# 3_Sensor.net
KiCad netlist of a schematic drawn in Altium Designer
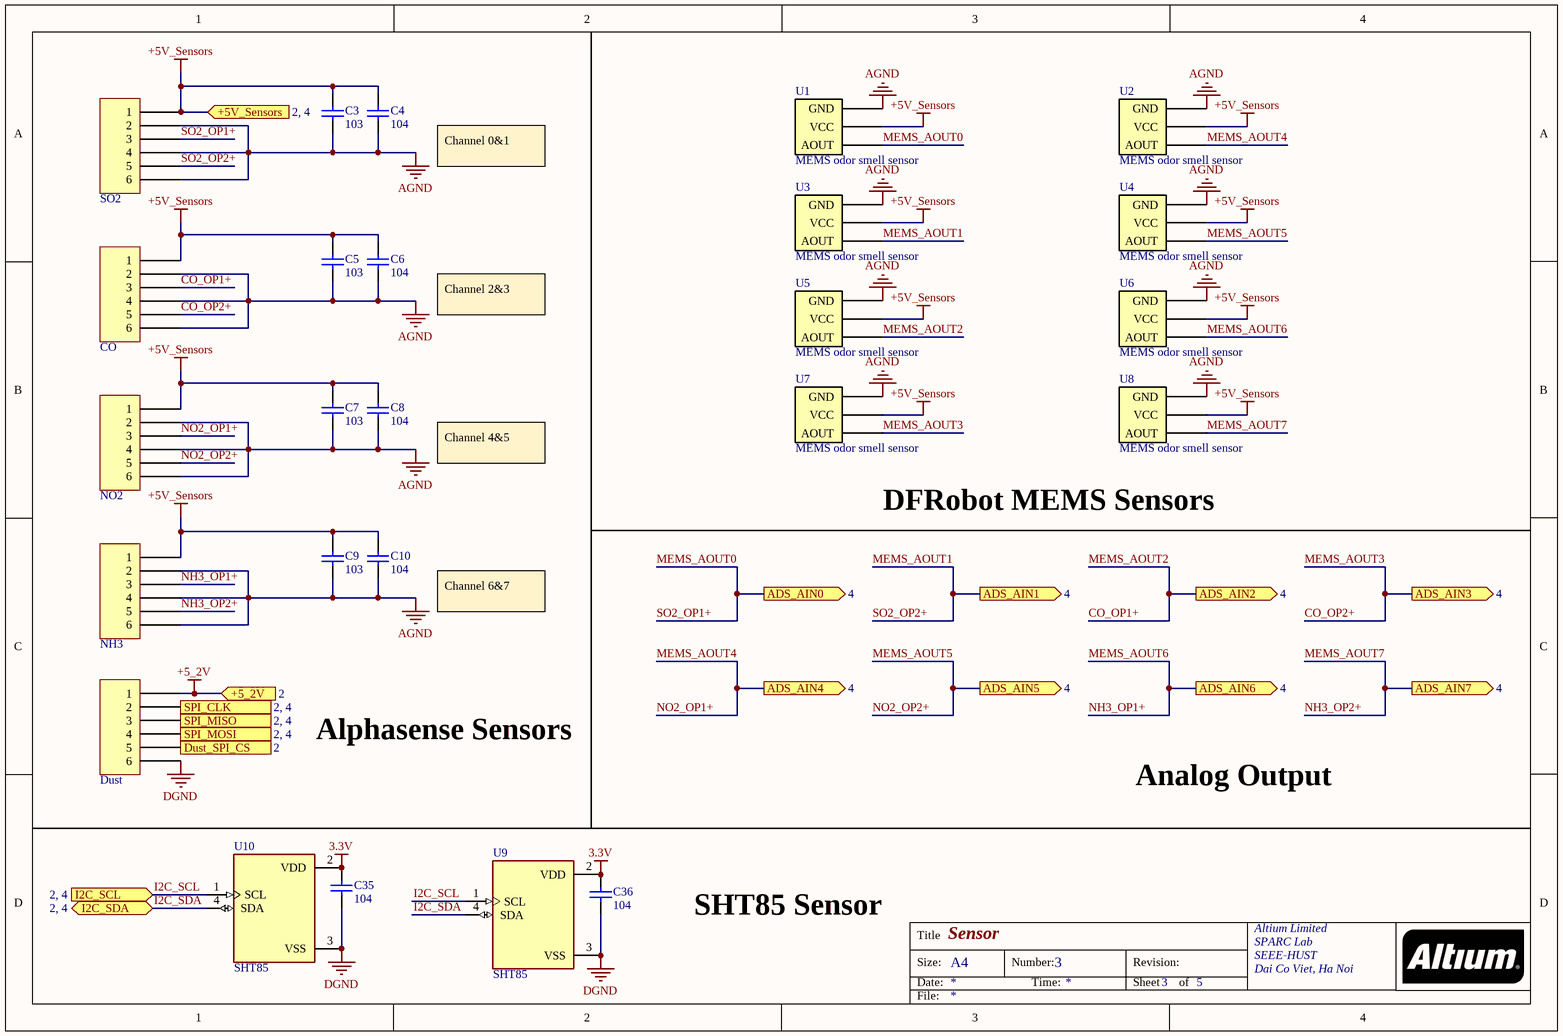
[diagram p0: [3]Sensor.SchDoc]

(export (version "E")
  (design (tool "Eeschema 10.0.6"))
  (components
    (comp (ref "C3")
      (value "103")
      (footprint "tu 0805")
      (description "Dán")
      (libsource (lib "Tu dien") (part "Tu 0805 103 50V 10%_1"))
    )
    (comp (ref "C4")
      (value "104")
      (footprint "tu 0805")
      (description "Dán")
      (libsource (lib "Tu dien") (part "Tu 0805 104 50V 10%"))
    )
    (comp (ref "C5")
      (value "103")
      (footprint "tu 0805")
      (description "Dán")
      (libsource (lib "Tu dien") (part "Tu 0805 103 50V 10%_1"))
    )
    (comp (ref "C6")
      (value "104")
      (footprint "tu 0805")
      (description "Dán")
      (libsource (lib "Tu dien") (part "Tu 0805 104 50V 10%"))
    )
    (comp (ref "C7")
      (value "103")
      (footprint "tu 0805")
      (description "Dán")
      (libsource (lib "Tu dien") (part "Tu 0805 103 50V 10%_1"))
    )
    (comp (ref "C8")
      (value "104")
      (footprint "tu 0805")
      (description "Dán")
      (libsource (lib "Tu dien") (part "Tu 0805 104 50V 10%"))
    )
    (comp (ref "C9")
      (value "103")
      (footprint "tu 0805")
      (description "Dán")
      (libsource (lib "Tu dien") (part "Tu 0805 103 50V 10%_1"))
    )
    (comp (ref "C10")
      (value "104")
      (footprint "tu 0805")
      (description "Dán")
      (libsource (lib "Tu dien") (part "Tu 0805 104 50V 10%"))
    )
    (comp (ref "C35")
      (value "104")
      (footprint "tu 0805")
      (description "Dán")
      (libsource (lib "Tu dien") (part "Tu 0805 104 50V 10%"))
    )
    (comp (ref "C36")
      (value "104")
      (footprint "tu 0805")
      (description "Dán")
      (libsource (lib "Tu dien") (part "Tu 0805 104 50V 10%"))
    )
    (comp (ref "H1") (value "SO2") (footprint "Header:Molex 6p") (libsource (lib "Header") (part "Molex 6p")))
    (comp (ref "H2") (value "CO") (footprint "Header:Molex 6p") (libsource (lib "Header") (part "Molex 6p")))
    (comp (ref "H3") (value "NO2") (footprint "Header:Molex 6p") (libsource (lib "Header") (part "Molex 6p")))
    (comp (ref "H4") (value "NH3") (footprint "Header:Molex 6p") (libsource (lib "Header") (part "Molex 6p")))
    (comp (ref "H5")
      (value "Dust")
      (footprint "Header:Molex 6p")
      (libsource (lib "Header") (part "Molex 6p"))
    )
    (comp (ref "U1")
      (value "MEMS odor smell sensor")
      (footprint "Module1:MEMS_odor_sensor")
      (description "DFRobot MEMS Odor Smell Gas Detection Sensor")
      (libsource (lib "Module1") (part "MEMS odor smell sensor"))
    )
    (comp (ref "U2")
      (value "MEMS odor smell sensor")
      (footprint "Module1:MEMS_odor_sensor")
      (description "DFRobot MEMS Odor Smell Gas Detection Sensor")
      (libsource (lib "Module1") (part "MEMS odor smell sensor"))
    )
    (comp (ref "U3")
      (value "MEMS odor smell sensor")
      (footprint "Module1:MEMS_odor_sensor")
      (description "DFRobot MEMS Odor Smell Gas Detection Sensor")
      (libsource (lib "Module1") (part "MEMS odor smell sensor"))
    )
    (comp (ref "U4")
      (value "MEMS odor smell sensor")
      (footprint "Module1:MEMS_odor_sensor")
      (description "DFRobot MEMS Odor Smell Gas Detection Sensor")
      (libsource (lib "Module1") (part "MEMS odor smell sensor"))
    )
    (comp (ref "U5")
      (value "MEMS odor smell sensor")
      (footprint "Module1:MEMS_odor_sensor")
      (description "DFRobot MEMS Odor Smell Gas Detection Sensor")
      (libsource (lib "Module1") (part "MEMS odor smell sensor"))
    )
    (comp (ref "U6")
      (value "MEMS odor smell sensor")
      (footprint "Module1:MEMS_odor_sensor")
      (description "DFRobot MEMS Odor Smell Gas Detection Sensor")
      (libsource (lib "Module1") (part "MEMS odor smell sensor"))
    )
    (comp (ref "U7")
      (value "MEMS odor smell sensor")
      (footprint "Module1:MEMS_odor_sensor")
      (description "DFRobot MEMS Odor Smell Gas Detection Sensor")
      (libsource (lib "Module1") (part "MEMS odor smell sensor"))
    )
    (comp (ref "U8")
      (value "MEMS odor smell sensor")
      (footprint "Module1:MEMS_odor_sensor")
      (description "DFRobot MEMS Odor Smell Gas Detection Sensor")
      (libsource (lib "Module1") (part "MEMS odor smell sensor"))
    )
    (comp (ref "U9")
      (value "SHT85")
      (footprint "Module1:XDCR_SHT85")
      (description "Humidity Temperature Sensor 0 ~ 100% RH Digital Â±1.5% RH 8s Through Hole")
      (fields (field (name "MF") "Sensirion AG") (field (name "DIGI-KEY_PART_NUMBER") "1649-1110-ND"))
      (libsource (lib "Module1") (part "SHT85"))
    )
    (comp (ref "U10")
      (value "SHT85")
      (footprint "Module1:XDCR_SHT85")
      (description "Humidity Temperature Sensor 0 ~ 100% RH Digital Â±1.5% RH 8s Through Hole")
      (fields (field (name "MF") "Sensirion AG") (field (name "DIGI-KEY_PART_NUMBER") "1649-1110-ND"))
      (libsource (lib "Module1") (part "SHT85"))
    )
  )
  (nets
    (net (code "1") (name "+5V_Sensors") (class "Default")
      (node (ref "C10") (pin "1") (pinfunction "1_1") (pintype "passive"))
      (node (ref "C3") (pin "1") (pinfunction "1_1") (pintype "passive"))
      (node (ref "C4") (pin "1") (pinfunction "1_1") (pintype "passive"))
      (node (ref "C5") (pin "1") (pinfunction "1_1") (pintype "passive"))
      (node (ref "C6") (pin "1") (pinfunction "1_1") (pintype "passive"))
      (node (ref "C7") (pin "1") (pinfunction "1_1") (pintype "passive"))
      (node (ref "C8") (pin "1") (pinfunction "1_1") (pintype "passive"))
      (node (ref "C9") (pin "1") (pinfunction "1_1") (pintype "passive"))
      (node (ref "H1") (pin "1") (pinfunction "1_1") (pintype "passive"))
      (node (ref "H2") (pin "1") (pinfunction "1_1") (pintype "passive"))
      (node (ref "H3") (pin "1") (pinfunction "1_1") (pintype "passive"))
      (node (ref "H4") (pin "1") (pinfunction "1_1") (pintype "passive"))
      (node (ref "U1") (pin "2") (pinfunction "VCC_2") (pintype "passive"))
      (node (ref "U2") (pin "2") (pinfunction "VCC_2") (pintype "passive"))
      (node (ref "U3") (pin "2") (pinfunction "VCC_2") (pintype "passive"))
      (node (ref "U4") (pin "2") (pinfunction "VCC_2") (pintype "passive"))
      (node (ref "U5") (pin "2") (pinfunction "VCC_2") (pintype "passive"))
      (node (ref "U6") (pin "2") (pinfunction "VCC_2") (pintype "passive"))
      (node (ref "U7") (pin "2") (pinfunction "VCC_2") (pintype "passive"))
      (node (ref "U8") (pin "2") (pinfunction "VCC_2") (pintype "passive"))
    )
    (net (code "2") (name "+5_2V") (class "Default")
      (node (ref "H5") (pin "1") (pinfunction "1_1") (pintype "passive"))
    )
    (net (code "3") (name "/CO_OP1+") (class "Default")
      (node (ref "H2") (pin "3") (pinfunction "3_3") (pintype "passive"))
      (node (ref "U5") (pin "3") (pinfunction "AOUT_3") (pintype "passive"))
    )
    (net (code "4") (name "/CO_OP2+") (class "Default")
      (node (ref "H2") (pin "5") (pinfunction "5_5") (pintype "passive"))
      (node (ref "U7") (pin "3") (pinfunction "AOUT_3") (pintype "passive"))
    )
    (net (code "5") (name "/Dust_SPI_CS") (class "Default")
      (node (ref "H5") (pin "5") (pinfunction "5_5") (pintype "passive"))
    )
    (net (code "6") (name "/I2C_SCL") (class "Default")
      (node (ref "U10") (pin "1") (pinfunction "SCL_1") (pintype "input"))
      (node (ref "U9") (pin "1") (pinfunction "SCL_1") (pintype "input"))
    )
    (net (code "7") (name "/I2C_SDA") (class "Default")
      (node (ref "U10") (pin "4") (pinfunction "SDA_4") (pintype "bidirectional"))
      (node (ref "U9") (pin "4") (pinfunction "SDA_4") (pintype "bidirectional"))
    )
    (net (code "8") (name "/MEMS_AOUT0") (class "Default")
      (node (ref "H1") (pin "3") (pinfunction "3_3") (pintype "passive"))
      (node (ref "U1") (pin "3") (pinfunction "AOUT_3") (pintype "passive"))
    )
    (net (code "9") (name "/MEMS_AOUT1") (class "Default")
      (node (ref "H1") (pin "5") (pinfunction "5_5") (pintype "passive"))
      (node (ref "U3") (pin "3") (pinfunction "AOUT_3") (pintype "passive"))
    )
    (net (code "10") (name "/MEMS_AOUT4") (class "Default")
      (node (ref "H3") (pin "3") (pinfunction "3_3") (pintype "passive"))
      (node (ref "U2") (pin "3") (pinfunction "AOUT_3") (pintype "passive"))
    )
    (net (code "11") (name "/MEMS_AOUT5") (class "Default")
      (node (ref "H3") (pin "5") (pinfunction "5_5") (pintype "passive"))
      (node (ref "U4") (pin "3") (pinfunction "AOUT_3") (pintype "passive"))
    )
    (net (code "12") (name "/MEMS_AOUT6") (class "Default")
      (node (ref "H4") (pin "3") (pinfunction "3_3") (pintype "passive"))
      (node (ref "U6") (pin "3") (pinfunction "AOUT_3") (pintype "passive"))
    )
    (net (code "13") (name "/MEMS_AOUT7") (class "Default")
      (node (ref "H4") (pin "5") (pinfunction "5_5") (pintype "passive"))
      (node (ref "U8") (pin "3") (pinfunction "AOUT_3") (pintype "passive"))
    )
    (net (code "14") (name "/SPI_CLK") (class "Default")
      (node (ref "H5") (pin "2") (pinfunction "2_2") (pintype "passive"))
    )
    (net (code "15") (name "/SPI_MISO") (class "Default")
      (node (ref "H5") (pin "3") (pinfunction "3_3") (pintype "passive"))
    )
    (net (code "16") (name "/SPI_MOSI") (class "Default")
      (node (ref "H5") (pin "4") (pinfunction "4_4") (pintype "passive"))
    )
    (net (code "17") (name "3.3V") (class "Default")
      (node (ref "C35") (pin "1") (pinfunction "1_1") (pintype "passive"))
      (node (ref "C36") (pin "1") (pinfunction "1_1") (pintype "passive"))
      (node (ref "U10") (pin "2") (pinfunction "VDD_2") (pintype "power_in"))
      (node (ref "U9") (pin "2") (pinfunction "VDD_2") (pintype "power_in"))
    )
    (net (code "18") (name "AGND") (class "Default")
      (node (ref "C10") (pin "2") (pinfunction "2_2") (pintype "passive"))
      (node (ref "C3") (pin "2") (pinfunction "2_2") (pintype "passive"))
      (node (ref "C4") (pin "2") (pinfunction "2_2") (pintype "passive"))
      (node (ref "C5") (pin "2") (pinfunction "2_2") (pintype "passive"))
      (node (ref "C6") (pin "2") (pinfunction "2_2") (pintype "passive"))
      (node (ref "C7") (pin "2") (pinfunction "2_2") (pintype "passive"))
      (node (ref "C8") (pin "2") (pinfunction "2_2") (pintype "passive"))
      (node (ref "C9") (pin "2") (pinfunction "2_2") (pintype "passive"))
      (node (ref "H1") (pin "2") (pinfunction "2_2") (pintype "passive"))
      (node (ref "H1") (pin "4") (pinfunction "4_4") (pintype "passive"))
      (node (ref "H1") (pin "6") (pinfunction "6_6") (pintype "passive"))
      (node (ref "H2") (pin "2") (pinfunction "2_2") (pintype "passive"))
      (node (ref "H2") (pin "4") (pinfunction "4_4") (pintype "passive"))
      (node (ref "H2") (pin "6") (pinfunction "6_6") (pintype "passive"))
      (node (ref "H3") (pin "2") (pinfunction "2_2") (pintype "passive"))
      (node (ref "H3") (pin "4") (pinfunction "4_4") (pintype "passive"))
      (node (ref "H3") (pin "6") (pinfunction "6_6") (pintype "passive"))
      (node (ref "H4") (pin "2") (pinfunction "2_2") (pintype "passive"))
      (node (ref "H4") (pin "4") (pinfunction "4_4") (pintype "passive"))
      (node (ref "H4") (pin "6") (pinfunction "6_6") (pintype "passive"))
      (node (ref "U1") (pin "1") (pinfunction "GND_1") (pintype "passive"))
      (node (ref "U2") (pin "1") (pinfunction "GND_1") (pintype "passive"))
      (node (ref "U3") (pin "1") (pinfunction "GND_1") (pintype "passive"))
      (node (ref "U4") (pin "1") (pinfunction "GND_1") (pintype "passive"))
      (node (ref "U5") (pin "1") (pinfunction "GND_1") (pintype "passive"))
      (node (ref "U6") (pin "1") (pinfunction "GND_1") (pintype "passive"))
      (node (ref "U7") (pin "1") (pinfunction "GND_1") (pintype "passive"))
      (node (ref "U8") (pin "1") (pinfunction "GND_1") (pintype "passive"))
    )
    (net (code "19") (name "DGND") (class "Default")
      (node (ref "C35") (pin "2") (pinfunction "2_2") (pintype "passive"))
      (node (ref "C36") (pin "2") (pinfunction "2_2") (pintype "passive"))
      (node (ref "H5") (pin "6") (pinfunction "6_6") (pintype "passive"))
      (node (ref "U10") (pin "3") (pinfunction "VSS_3") (pintype "power_in"))
      (node (ref "U9") (pin "3") (pinfunction "VSS_3") (pintype "power_in"))
    )
  )
)
